# Controller.net
KiCad netlist of a schematic drawn in EAGLE
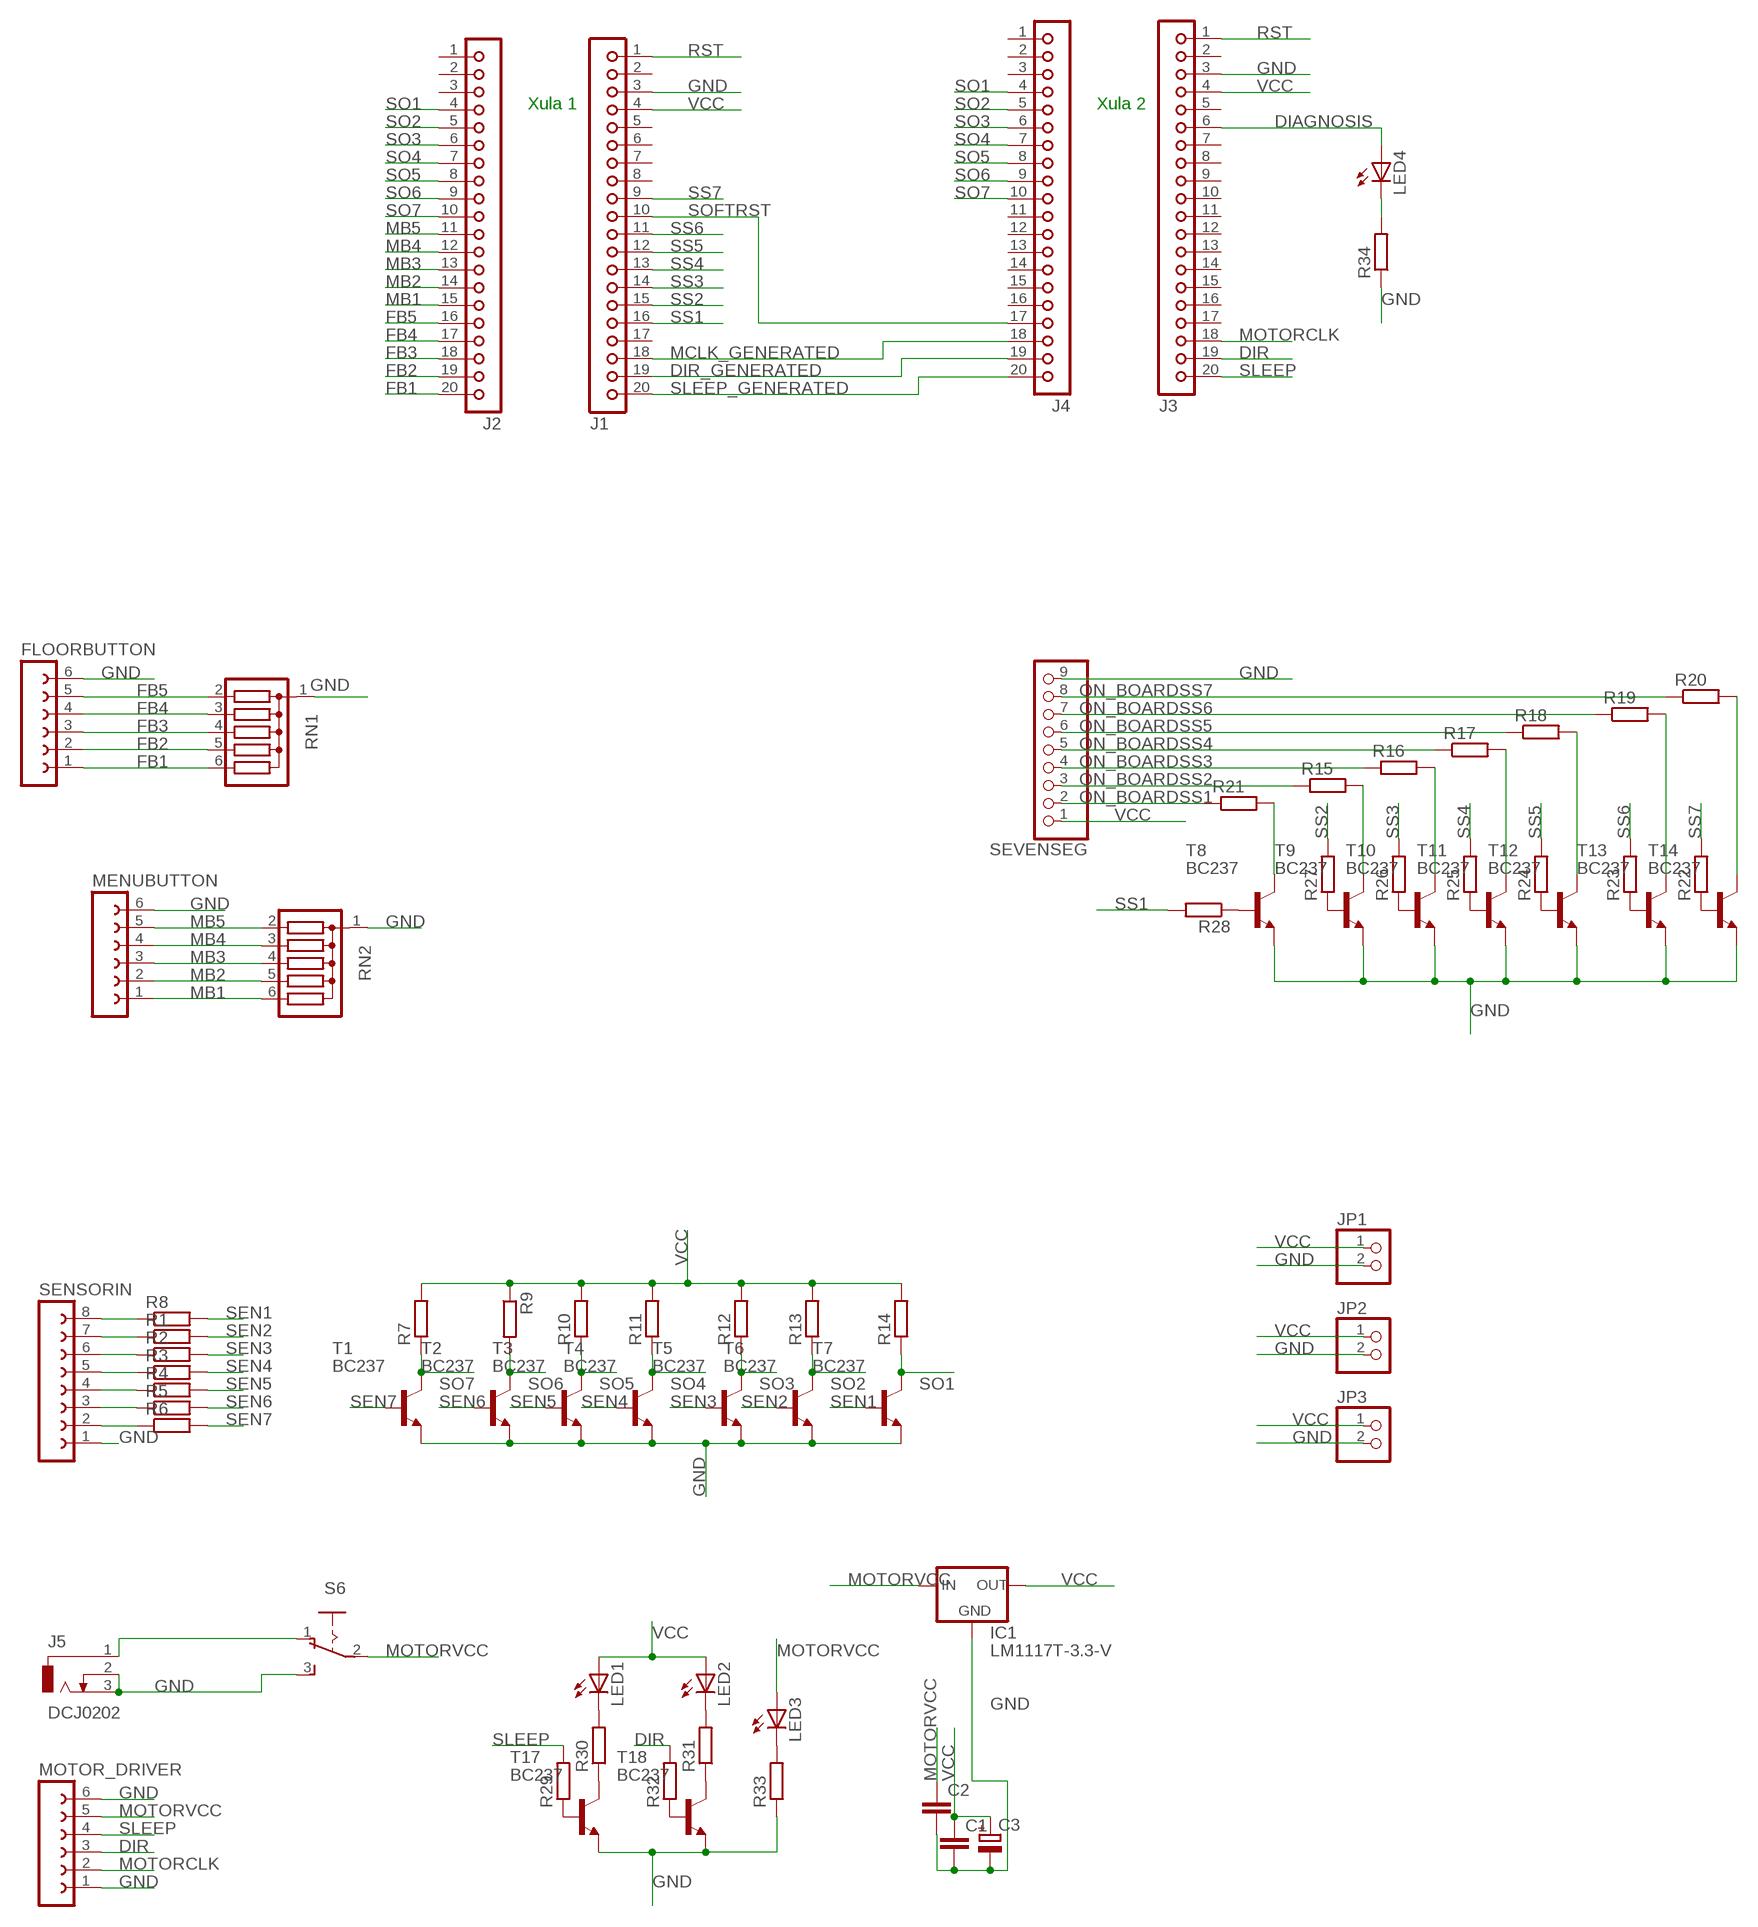
[diagram p0: schematic, sheet 1]

(export (version "E")
  (design (tool "Eeschema 10.0.6"))
  (components
    (comp (ref "C1")
      (value "C-EU025-025X050")
      (footprint "eagle-import:C025-025X050")
      (libsource (lib "eagle-import") (part "C-EU025-025X050"))
    )
    (comp (ref "C2")
      (value "C-EU025-025X050")
      (footprint "eagle-import:C025-025X050")
      (libsource (lib "eagle-import") (part "C-EU025-025X050"))
    )
    (comp (ref "C3")
      (value "CPOL-EUE3.5-8")
      (footprint "eagle-import:E3,5-8")
      (libsource (lib "eagle-import") (part "CPOL-EUE3.5-8"))
    )
    (comp (ref "FLOORBUTTON")
      (value "FE06-1")
      (footprint "eagle-import:FE06")
      (libsource (lib "eagle-import") (part "FE06-1"))
    )
    (comp (ref "IC1")
      (value "LM1117T-3.3-V")
      (footprint "eagle-import:TO220V")
      (libsource (lib "eagle-import") (part "LM1117T--V3.3"))
    )
    (comp (ref "J1")
      (value "JBK20")
      (footprint "eagle-import:JBK20")
      (libsource (lib "eagle-import") (part "JBK20"))
    )
    (comp (ref "J2")
      (value "JBK20")
      (footprint "eagle-import:JBK20")
      (libsource (lib "eagle-import") (part "JBK20"))
    )
    (comp (ref "J3")
      (value "JBK20")
      (footprint "eagle-import:JBK20")
      (libsource (lib "eagle-import") (part "JBK20"))
    )
    (comp (ref "J4")
      (value "JBK20")
      (footprint "eagle-import:JBK20")
      (libsource (lib "eagle-import") (part "JBK20"))
    )
    (comp (ref "J5")
      (value "DCJ0202")
      (footprint "eagle-import:DCJ0202")
      (libsource (lib "eagle-import") (part "DCJ0202"))
    )
    (comp (ref "JP1")
      (value "PINHD-1X2")
      (footprint "eagle-import:1X02")
      (libsource (lib "eagle-import") (part "PINHD-1X2"))
    )
    (comp (ref "JP2")
      (value "PINHD-1X2")
      (footprint "eagle-import:1X02")
      (libsource (lib "eagle-import") (part "PINHD-1X2"))
    )
    (comp (ref "JP3")
      (value "PINHD-1X2")
      (footprint "eagle-import:1X02")
      (libsource (lib "eagle-import") (part "PINHD-1X2"))
    )
    (comp (ref "LED1")
      (value "LED3MM")
      (footprint "eagle-import:LED3MM")
      (libsource (lib "eagle-import") (part "LED3MM"))
    )
    (comp (ref "LED2")
      (value "LED3MM")
      (footprint "eagle-import:LED3MM")
      (libsource (lib "eagle-import") (part "LED3MM"))
    )
    (comp (ref "LED3")
      (value "LED3MM")
      (footprint "eagle-import:LED3MM")
      (libsource (lib "eagle-import") (part "LED3MM"))
    )
    (comp (ref "LED4")
      (value "LED3MM")
      (footprint "eagle-import:LED3MM")
      (libsource (lib "eagle-import") (part "LED3MM"))
    )
    (comp (ref "MENUBUTTON")
      (value "FE06-1")
      (footprint "eagle-import:FE06")
      (libsource (lib "eagle-import") (part "FE06-1"))
    )
    (comp (ref "MOTOR_DRIVER")
      (value "FE06-1")
      (footprint "eagle-import:FE06")
      (libsource (lib "eagle-import") (part "FE06-1"))
    )
    (comp (ref "R1")
      (value "R-EU_0204/5")
      (footprint "eagle-import:0204_5")
      (libsource (lib "eagle-import") (part "R-EU_0204/5"))
    )
    (comp (ref "R2")
      (value "R-EU_0204/5")
      (footprint "eagle-import:0204_5")
      (libsource (lib "eagle-import") (part "R-EU_0204/5"))
    )
    (comp (ref "R3")
      (value "R-EU_0204/5")
      (footprint "eagle-import:0204_5")
      (libsource (lib "eagle-import") (part "R-EU_0204/5"))
    )
    (comp (ref "R4")
      (value "R-EU_0204/5")
      (footprint "eagle-import:0204_5")
      (libsource (lib "eagle-import") (part "R-EU_0204/5"))
    )
    (comp (ref "R5")
      (value "R-EU_0204/5")
      (footprint "eagle-import:0204_5")
      (libsource (lib "eagle-import") (part "R-EU_0204/5"))
    )
    (comp (ref "R6")
      (value "R-EU_0204/5")
      (footprint "eagle-import:0204_5")
      (libsource (lib "eagle-import") (part "R-EU_0204/5"))
    )
    (comp (ref "R7")
      (value "R-EU_0204/5")
      (footprint "eagle-import:0204_5")
      (libsource (lib "eagle-import") (part "R-EU_0204/5"))
    )
    (comp (ref "R8")
      (value "R-EU_0204/5")
      (footprint "eagle-import:0204_5")
      (libsource (lib "eagle-import") (part "R-EU_0204/5"))
    )
    (comp (ref "R9")
      (value "R-EU_0204/5")
      (footprint "eagle-import:0204_5")
      (libsource (lib "eagle-import") (part "R-EU_0204/5"))
    )
    (comp (ref "R10")
      (value "R-EU_0204/5")
      (footprint "eagle-import:0204_5")
      (libsource (lib "eagle-import") (part "R-EU_0204/5"))
    )
    (comp (ref "R11")
      (value "R-EU_0204/5")
      (footprint "eagle-import:0204_5")
      (libsource (lib "eagle-import") (part "R-EU_0204/5"))
    )
    (comp (ref "R12")
      (value "R-EU_0204/5")
      (footprint "eagle-import:0204_5")
      (libsource (lib "eagle-import") (part "R-EU_0204/5"))
    )
    (comp (ref "R13")
      (value "R-EU_0204/5")
      (footprint "eagle-import:0204_5")
      (libsource (lib "eagle-import") (part "R-EU_0204/5"))
    )
    (comp (ref "R14")
      (value "R-EU_0204/5")
      (footprint "eagle-import:0204_5")
      (libsource (lib "eagle-import") (part "R-EU_0204/5"))
    )
    (comp (ref "R15")
      (value "R-EU_0204/5")
      (footprint "eagle-import:0204_5")
      (libsource (lib "eagle-import") (part "R-EU_0204/5"))
    )
    (comp (ref "R16")
      (value "R-EU_0204/5")
      (footprint "eagle-import:0204_5")
      (libsource (lib "eagle-import") (part "R-EU_0204/5"))
    )
    (comp (ref "R17")
      (value "R-EU_0204/5")
      (footprint "eagle-import:0204_5")
      (libsource (lib "eagle-import") (part "R-EU_0204/5"))
    )
    (comp (ref "R18")
      (value "R-EU_0204/5")
      (footprint "eagle-import:0204_5")
      (libsource (lib "eagle-import") (part "R-EU_0204/5"))
    )
    (comp (ref "R19")
      (value "R-EU_0204/5")
      (footprint "eagle-import:0204_5")
      (libsource (lib "eagle-import") (part "R-EU_0204/5"))
    )
    (comp (ref "R20")
      (value "R-EU_0204/5")
      (footprint "eagle-import:0204_5")
      (libsource (lib "eagle-import") (part "R-EU_0204/5"))
    )
    (comp (ref "R21")
      (value "R-EU_0204/5")
      (footprint "eagle-import:0204_5")
      (libsource (lib "eagle-import") (part "R-EU_0204/5"))
    )
    (comp (ref "R22")
      (value "R-EU_0204/5")
      (footprint "eagle-import:0204_5")
      (libsource (lib "eagle-import") (part "R-EU_0204/5"))
    )
    (comp (ref "R23")
      (value "R-EU_0204/5")
      (footprint "eagle-import:0204_5")
      (libsource (lib "eagle-import") (part "R-EU_0204/5"))
    )
    (comp (ref "R24")
      (value "R-EU_0204/5")
      (footprint "eagle-import:0204_5")
      (libsource (lib "eagle-import") (part "R-EU_0204/5"))
    )
    (comp (ref "R25")
      (value "R-EU_0204/5")
      (footprint "eagle-import:0204_5")
      (libsource (lib "eagle-import") (part "R-EU_0204/5"))
    )
    (comp (ref "R26")
      (value "R-EU_0204/5")
      (footprint "eagle-import:0204_5")
      (libsource (lib "eagle-import") (part "R-EU_0204/5"))
    )
    (comp (ref "R27")
      (value "R-EU_0204/5")
      (footprint "eagle-import:0204_5")
      (libsource (lib "eagle-import") (part "R-EU_0204/5"))
    )
    (comp (ref "R28")
      (value "R-EU_0204/5")
      (footprint "eagle-import:0204_5")
      (libsource (lib "eagle-import") (part "R-EU_0204/5"))
    )
    (comp (ref "R29")
      (value "R-EU_0204/5")
      (footprint "eagle-import:0204_5")
      (libsource (lib "eagle-import") (part "R-EU_0204/5"))
    )
    (comp (ref "R30")
      (value "R-EU_0204/5")
      (footprint "eagle-import:0204_5")
      (libsource (lib "eagle-import") (part "R-EU_0204/5"))
    )
    (comp (ref "R31")
      (value "R-EU_0204/5")
      (footprint "eagle-import:0204_5")
      (libsource (lib "eagle-import") (part "R-EU_0204/5"))
    )
    (comp (ref "R32")
      (value "R-EU_0204/5")
      (footprint "eagle-import:0204_5")
      (libsource (lib "eagle-import") (part "R-EU_0204/5"))
    )
    (comp (ref "R33")
      (value "R-EU_0204/5")
      (footprint "eagle-import:0204_5")
      (libsource (lib "eagle-import") (part "R-EU_0204/5"))
    )
    (comp (ref "R34")
      (value "R-EU_0204/5")
      (footprint "eagle-import:0204_5")
      (libsource (lib "eagle-import") (part "R-EU_0204/5"))
    )
    (comp (ref "RN1")
      (value "G05R")
      (footprint "eagle-import:SIL6")
      (libsource (lib "eagle-import") (part "G05R"))
    )
    (comp (ref "RN2")
      (value "G05R")
      (footprint "eagle-import:SIL6")
      (libsource (lib "eagle-import") (part "G05R"))
    )
    (comp (ref "S6")
      (value "255SB")
      (footprint "eagle-import:255SB")
      (libsource (lib "eagle-import") (part "255SB"))
    )
    (comp (ref "SENSORIN")
      (value "FE08-1")
      (footprint "eagle-import:FE08")
      (libsource (lib "eagle-import") (part "FE08-1"))
    )
    (comp (ref "SEVENSEG")
      (value "PINHD-1X9")
      (footprint "eagle-import:1X09-BIG")
      (libsource (lib "eagle-import") (part "PINHD-1X9"))
    )
    (comp (ref "T1")
      (value "BC237")
      (footprint "eagle-import:TO92")
      (libsource (lib "eagle-import") (part "BC237"))
    )
    (comp (ref "T2")
      (value "BC237")
      (footprint "eagle-import:TO92")
      (libsource (lib "eagle-import") (part "BC237"))
    )
    (comp (ref "T3")
      (value "BC237")
      (footprint "eagle-import:TO92")
      (libsource (lib "eagle-import") (part "BC237"))
    )
    (comp (ref "T4")
      (value "BC237")
      (footprint "eagle-import:TO92")
      (libsource (lib "eagle-import") (part "BC237"))
    )
    (comp (ref "T5")
      (value "BC237")
      (footprint "eagle-import:TO92")
      (libsource (lib "eagle-import") (part "BC237"))
    )
    (comp (ref "T6")
      (value "BC237")
      (footprint "eagle-import:TO92")
      (libsource (lib "eagle-import") (part "BC237"))
    )
    (comp (ref "T7")
      (value "BC237")
      (footprint "eagle-import:TO92")
      (libsource (lib "eagle-import") (part "BC237"))
    )
    (comp (ref "T8")
      (value "BC237")
      (footprint "eagle-import:TO92")
      (libsource (lib "eagle-import") (part "BC237"))
    )
    (comp (ref "T9")
      (value "BC237")
      (footprint "eagle-import:TO92")
      (libsource (lib "eagle-import") (part "BC237"))
    )
    (comp (ref "T10")
      (value "BC237")
      (footprint "eagle-import:TO92")
      (libsource (lib "eagle-import") (part "BC237"))
    )
    (comp (ref "T11")
      (value "BC237")
      (footprint "eagle-import:TO92")
      (libsource (lib "eagle-import") (part "BC237"))
    )
    (comp (ref "T12")
      (value "BC237")
      (footprint "eagle-import:TO92")
      (libsource (lib "eagle-import") (part "BC237"))
    )
    (comp (ref "T13")
      (value "BC237")
      (footprint "eagle-import:TO92")
      (libsource (lib "eagle-import") (part "BC237"))
    )
    (comp (ref "T14")
      (value "BC237")
      (footprint "eagle-import:TO92")
      (libsource (lib "eagle-import") (part "BC237"))
    )
    (comp (ref "T17")
      (value "BC237")
      (footprint "eagle-import:TO92")
      (libsource (lib "eagle-import") (part "BC237"))
    )
    (comp (ref "T18")
      (value "BC237")
      (footprint "eagle-import:TO92")
      (libsource (lib "eagle-import") (part "BC237"))
    )
  )
  (nets
    (net (code "1") (name "/DIAGNOSIS") (class "Default")
      (node (ref "J3") (pin "6") (pinfunction "6_6") (pintype "passive"))
      (node (ref "LED4") (pin "A") (pinfunction "A_A") (pintype "passive"))
    )
    (net (code "2") (name "/DIR") (class "Default")
      (node (ref "J3") (pin "19") (pinfunction "19_19") (pintype "passive"))
      (node (ref "MOTOR_DRIVER") (pin "3") (pinfunction "3_3") (pintype "passive"))
      (node (ref "R32") (pin "2") (pinfunction "2_2") (pintype "passive"))
    )
    (net (code "3") (name "/DIR_GENERATED") (class "Default")
      (node (ref "J1") (pin "19") (pinfunction "19_19") (pintype "passive"))
      (node (ref "J4") (pin "19") (pinfunction "19_19") (pintype "passive"))
    )
    (net (code "4") (name "/FB1") (class "Default")
      (node (ref "FLOORBUTTON") (pin "1") (pinfunction "1_1") (pintype "passive"))
      (node (ref "J2") (pin "20") (pinfunction "20_20") (pintype "passive"))
      (node (ref "RN1") (pin "6") (pinfunction "6_6") (pintype "passive"))
    )
    (net (code "5") (name "/FB2") (class "Default")
      (node (ref "FLOORBUTTON") (pin "2") (pinfunction "2_2") (pintype "passive"))
      (node (ref "J2") (pin "19") (pinfunction "19_19") (pintype "passive"))
      (node (ref "RN1") (pin "5") (pinfunction "5_5") (pintype "passive"))
    )
    (net (code "6") (name "/FB3") (class "Default")
      (node (ref "FLOORBUTTON") (pin "3") (pinfunction "3_3") (pintype "passive"))
      (node (ref "J2") (pin "18") (pinfunction "18_18") (pintype "passive"))
      (node (ref "RN1") (pin "4") (pinfunction "4_4") (pintype "passive"))
    )
    (net (code "7") (name "/FB4") (class "Default")
      (node (ref "FLOORBUTTON") (pin "4") (pinfunction "4_4") (pintype "passive"))
      (node (ref "J2") (pin "17") (pinfunction "17_17") (pintype "passive"))
      (node (ref "RN1") (pin "3") (pinfunction "3_3") (pintype "passive"))
    )
    (net (code "8") (name "/FB5") (class "Default")
      (node (ref "FLOORBUTTON") (pin "5") (pinfunction "5_5") (pintype "passive"))
      (node (ref "J2") (pin "16") (pinfunction "16_16") (pintype "passive"))
      (node (ref "RN1") (pin "2") (pinfunction "2_2") (pintype "passive"))
    )
    (net (code "9") (name "/GND") (class "Default")
      (node (ref "C1") (pin "2") (pinfunction "2_2") (pintype "passive"))
      (node (ref "C2") (pin "2") (pinfunction "2_2") (pintype "passive"))
      (node (ref "C3") (pin "-") (pinfunction "-_-") (pintype "passive"))
      (node (ref "FLOORBUTTON") (pin "6") (pinfunction "6_6") (pintype "passive"))
      (node (ref "IC1") (pin "1") (pinfunction "GND_1") (pintype "input"))
      (node (ref "J1") (pin "3") (pinfunction "3_3") (pintype "passive"))
      (node (ref "J3") (pin "3") (pinfunction "3_3") (pintype "passive"))
      (node (ref "J5") (pin "2") (pinfunction "2_2") (pintype "passive"))
      (node (ref "J5") (pin "3") (pinfunction "3_3") (pintype "passive"))
      (node (ref "JP1") (pin "2") (pinfunction "2_2") (pintype "passive"))
      (node (ref "JP2") (pin "2") (pinfunction "2_2") (pintype "passive"))
      (node (ref "JP3") (pin "2") (pinfunction "2_2") (pintype "passive"))
      (node (ref "MENUBUTTON") (pin "6") (pinfunction "6_6") (pintype "passive"))
      (node (ref "MOTOR_DRIVER") (pin "1") (pinfunction "1_1") (pintype "passive"))
      (node (ref "MOTOR_DRIVER") (pin "6") (pinfunction "6_6") (pintype "passive"))
      (node (ref "R33") (pin "1") (pinfunction "1_1") (pintype "passive"))
      (node (ref "R34") (pin "1") (pinfunction "1_1") (pintype "passive"))
      (node (ref "RN1") (pin "1") (pinfunction "1_1") (pintype "passive"))
      (node (ref "RN2") (pin "1") (pinfunction "1_1") (pintype "passive"))
      (node (ref "S6") (pin "3") (pinfunction "S_3") (pintype "passive"))
      (node (ref "SENSORIN") (pin "1") (pinfunction "1_1") (pintype "passive"))
      (node (ref "SEVENSEG") (pin "9") (pinfunction "9_9") (pintype "passive"))
      (node (ref "T1") (pin "1") (pinfunction "E_1") (pintype "passive"))
      (node (ref "T10") (pin "1") (pinfunction "E_1") (pintype "passive"))
      (node (ref "T11") (pin "1") (pinfunction "E_1") (pintype "passive"))
      (node (ref "T12") (pin "1") (pinfunction "E_1") (pintype "passive"))
      (node (ref "T13") (pin "1") (pinfunction "E_1") (pintype "passive"))
      (node (ref "T14") (pin "1") (pinfunction "E_1") (pintype "passive"))
      (node (ref "T17") (pin "1") (pinfunction "E_1") (pintype "passive"))
      (node (ref "T18") (pin "1") (pinfunction "E_1") (pintype "passive"))
      (node (ref "T2") (pin "1") (pinfunction "E_1") (pintype "passive"))
      (node (ref "T3") (pin "1") (pinfunction "E_1") (pintype "passive"))
      (node (ref "T4") (pin "1") (pinfunction "E_1") (pintype "passive"))
      (node (ref "T5") (pin "1") (pinfunction "E_1") (pintype "passive"))
      (node (ref "T6") (pin "1") (pinfunction "E_1") (pintype "passive"))
      (node (ref "T7") (pin "1") (pinfunction "E_1") (pintype "passive"))
      (node (ref "T8") (pin "1") (pinfunction "E_1") (pintype "passive"))
      (node (ref "T9") (pin "1") (pinfunction "E_1") (pintype "passive"))
    )
    (net (code "10") (name "/MB1") (class "Default")
      (node (ref "J2") (pin "15") (pinfunction "15_15") (pintype "passive"))
      (node (ref "MENUBUTTON") (pin "1") (pinfunction "1_1") (pintype "passive"))
      (node (ref "RN2") (pin "6") (pinfunction "6_6") (pintype "passive"))
    )
    (net (code "11") (name "/MB2") (class "Default")
      (node (ref "J2") (pin "14") (pinfunction "14_14") (pintype "passive"))
      (node (ref "MENUBUTTON") (pin "2") (pinfunction "2_2") (pintype "passive"))
      (node (ref "RN2") (pin "5") (pinfunction "5_5") (pintype "passive"))
    )
    (net (code "12") (name "/MB3") (class "Default")
      (node (ref "J2") (pin "13") (pinfunction "13_13") (pintype "passive"))
      (node (ref "MENUBUTTON") (pin "3") (pinfunction "3_3") (pintype "passive"))
      (node (ref "RN2") (pin "4") (pinfunction "4_4") (pintype "passive"))
    )
    (net (code "13") (name "/MB4") (class "Default")
      (node (ref "J2") (pin "12") (pinfunction "12_12") (pintype "passive"))
      (node (ref "MENUBUTTON") (pin "4") (pinfunction "4_4") (pintype "passive"))
      (node (ref "RN2") (pin "3") (pinfunction "3_3") (pintype "passive"))
    )
    (net (code "14") (name "/MB5") (class "Default")
      (node (ref "J2") (pin "11") (pinfunction "11_11") (pintype "passive"))
      (node (ref "MENUBUTTON") (pin "5") (pinfunction "5_5") (pintype "passive"))
      (node (ref "RN2") (pin "2") (pinfunction "2_2") (pintype "passive"))
    )
    (net (code "15") (name "/MCLK_GENERATED") (class "Default")
      (node (ref "J1") (pin "18") (pinfunction "18_18") (pintype "passive"))
      (node (ref "J4") (pin "18") (pinfunction "18_18") (pintype "passive"))
    )
    (net (code "16") (name "/MOTORCLK") (class "Default")
      (node (ref "J3") (pin "18") (pinfunction "18_18") (pintype "passive"))
      (node (ref "MOTOR_DRIVER") (pin "2") (pinfunction "2_2") (pintype "passive"))
    )
    (net (code "17") (name "/MOTORVCC") (class "Default")
      (node (ref "C2") (pin "1") (pinfunction "1_1") (pintype "passive"))
      (node (ref "IC1") (pin "3") (pinfunction "IN_3") (pintype "input"))
      (node (ref "LED3") (pin "A") (pinfunction "A_A") (pintype "passive"))
      (node (ref "MOTOR_DRIVER") (pin "5") (pinfunction "5_5") (pintype "passive"))
      (node (ref "S6") (pin "2") (pinfunction "P_2") (pintype "passive"))
    )
    (net (code "18") (name "/ON_BOARDSS1") (class "Default")
      (node (ref "R21") (pin "1") (pinfunction "1_1") (pintype "passive"))
      (node (ref "SEVENSEG") (pin "2") (pinfunction "2_2") (pintype "passive"))
    )
    (net (code "19") (name "/ON_BOARDSS2") (class "Default")
      (node (ref "R15") (pin "1") (pinfunction "1_1") (pintype "passive"))
      (node (ref "SEVENSEG") (pin "3") (pinfunction "3_3") (pintype "passive"))
    )
    (net (code "20") (name "/ON_BOARDSS3") (class "Default")
      (node (ref "R16") (pin "1") (pinfunction "1_1") (pintype "passive"))
      (node (ref "SEVENSEG") (pin "4") (pinfunction "4_4") (pintype "passive"))
    )
    (net (code "21") (name "/ON_BOARDSS4") (class "Default")
      (node (ref "R17") (pin "1") (pinfunction "1_1") (pintype "passive"))
      (node (ref "SEVENSEG") (pin "5") (pinfunction "5_5") (pintype "passive"))
    )
    (net (code "22") (name "/ON_BOARDSS5") (class "Default")
      (node (ref "R18") (pin "1") (pinfunction "1_1") (pintype "passive"))
      (node (ref "SEVENSEG") (pin "6") (pinfunction "6_6") (pintype "passive"))
    )
    (net (code "23") (name "/ON_BOARDSS6") (class "Default")
      (node (ref "R19") (pin "1") (pinfunction "1_1") (pintype "passive"))
      (node (ref "SEVENSEG") (pin "7") (pinfunction "7_7") (pintype "passive"))
    )
    (net (code "24") (name "/ON_BOARDSS7") (class "Default")
      (node (ref "R20") (pin "1") (pinfunction "1_1") (pintype "passive"))
      (node (ref "SEVENSEG") (pin "8") (pinfunction "8_8") (pintype "passive"))
    )
    (net (code "25") (name "/RST") (class "Default")
      (node (ref "J1") (pin "1") (pinfunction "1_1") (pintype "passive"))
      (node (ref "J3") (pin "1") (pinfunction "1_1") (pintype "passive"))
    )
    (net (code "26") (name "/SEN1") (class "Default")
      (node (ref "R8") (pin "2") (pinfunction "2_2") (pintype "passive"))
      (node (ref "T7") (pin "2") (pinfunction "B_2") (pintype "passive"))
    )
    (net (code "27") (name "/SEN2") (class "Default")
      (node (ref "R1") (pin "2") (pinfunction "2_2") (pintype "passive"))
      (node (ref "T6") (pin "2") (pinfunction "B_2") (pintype "passive"))
    )
    (net (code "28") (name "/SEN3") (class "Default")
      (node (ref "R2") (pin "2") (pinfunction "2_2") (pintype "passive"))
      (node (ref "T5") (pin "2") (pinfunction "B_2") (pintype "passive"))
    )
    (net (code "29") (name "/SEN4") (class "Default")
      (node (ref "R3") (pin "2") (pinfunction "2_2") (pintype "passive"))
      (node (ref "T4") (pin "2") (pinfunction "B_2") (pintype "passive"))
    )
    (net (code "30") (name "/SEN5") (class "Default")
      (node (ref "R4") (pin "2") (pinfunction "2_2") (pintype "passive"))
      (node (ref "T3") (pin "2") (pinfunction "B_2") (pintype "passive"))
    )
    (net (code "31") (name "/SEN6") (class "Default")
      (node (ref "R5") (pin "2") (pinfunction "2_2") (pintype "passive"))
      (node (ref "T2") (pin "2") (pinfunction "B_2") (pintype "passive"))
    )
    (net (code "32") (name "/SEN7") (class "Default")
      (node (ref "R6") (pin "2") (pinfunction "2_2") (pintype "passive"))
      (node (ref "T1") (pin "2") (pinfunction "B_2") (pintype "passive"))
    )
    (net (code "33") (name "/SLEEP") (class "Default")
      (node (ref "J3") (pin "20") (pinfunction "20_20") (pintype "passive"))
      (node (ref "MOTOR_DRIVER") (pin "4") (pinfunction "4_4") (pintype "passive"))
      (node (ref "R29") (pin "2") (pinfunction "2_2") (pintype "passive"))
    )
    (net (code "34") (name "/SLEEP_GENERATED") (class "Default")
      (node (ref "J1") (pin "20") (pinfunction "20_20") (pintype "passive"))
      (node (ref "J4") (pin "20") (pinfunction "20_20") (pintype "passive"))
    )
    (net (code "35") (name "/SO1") (class "Default")
      (node (ref "J2") (pin "4") (pinfunction "4_4") (pintype "passive"))
      (node (ref "J4") (pin "4") (pinfunction "4_4") (pintype "passive"))
      (node (ref "R14") (pin "1") (pinfunction "1_1") (pintype "passive"))
      (node (ref "T7") (pin "3") (pinfunction "C_3") (pintype "passive"))
    )
    (net (code "36") (name "/SO2") (class "Default")
      (node (ref "J2") (pin "5") (pinfunction "5_5") (pintype "passive"))
      (node (ref "J4") (pin "5") (pinfunction "5_5") (pintype "passive"))
      (node (ref "R13") (pin "1") (pinfunction "1_1") (pintype "passive"))
      (node (ref "T6") (pin "3") (pinfunction "C_3") (pintype "passive"))
    )
    (net (code "37") (name "/SO3") (class "Default")
      (node (ref "J2") (pin "6") (pinfunction "6_6") (pintype "passive"))
      (node (ref "J4") (pin "6") (pinfunction "6_6") (pintype "passive"))
      (node (ref "R12") (pin "1") (pinfunction "1_1") (pintype "passive"))
      (node (ref "T5") (pin "3") (pinfunction "C_3") (pintype "passive"))
    )
    (net (code "38") (name "/SO4") (class "Default")
      (node (ref "J2") (pin "7") (pinfunction "7_7") (pintype "passive"))
      (node (ref "J4") (pin "7") (pinfunction "7_7") (pintype "passive"))
      (node (ref "R11") (pin "1") (pinfunction "1_1") (pintype "passive"))
      (node (ref "T4") (pin "3") (pinfunction "C_3") (pintype "passive"))
    )
    (net (code "39") (name "/SO5") (class "Default")
      (node (ref "J2") (pin "8") (pinfunction "8_8") (pintype "passive"))
      (node (ref "J4") (pin "8") (pinfunction "8_8") (pintype "passive"))
      (node (ref "R10") (pin "1") (pinfunction "1_1") (pintype "passive"))
      (node (ref "T3") (pin "3") (pinfunction "C_3") (pintype "passive"))
    )
    (net (code "40") (name "/SO6") (class "Default")
      (node (ref "J2") (pin "9") (pinfunction "9_9") (pintype "passive"))
      (node (ref "J4") (pin "9") (pinfunction "9_9") (pintype "passive"))
      (node (ref "R9") (pin "2") (pinfunction "2_2") (pintype "passive"))
      (node (ref "T2") (pin "3") (pinfunction "C_3") (pintype "passive"))
    )
    (net (code "41") (name "/SO7") (class "Default")
      (node (ref "J2") (pin "10") (pinfunction "10_10") (pintype "passive"))
      (node (ref "J4") (pin "10") (pinfunction "10_10") (pintype "passive"))
      (node (ref "R7") (pin "1") (pinfunction "1_1") (pintype "passive"))
      (node (ref "T1") (pin "3") (pinfunction "C_3") (pintype "passive"))
    )
    (net (code "42") (name "/SOFTRST") (class "Default")
      (node (ref "J1") (pin "10") (pinfunction "10_10") (pintype "passive"))
      (node (ref "J4") (pin "17") (pinfunction "17_17") (pintype "passive"))
    )
    (net (code "43") (name "/SS1") (class "Default")
      (node (ref "J1") (pin "16") (pinfunction "16_16") (pintype "passive"))
      (node (ref "R28") (pin "2") (pinfunction "2_2") (pintype "passive"))
    )
    (net (code "44") (name "/SS2") (class "Default")
      (node (ref "J1") (pin "15") (pinfunction "15_15") (pintype "passive"))
      (node (ref "R27") (pin "2") (pinfunction "2_2") (pintype "passive"))
    )
    (net (code "45") (name "/SS3") (class "Default")
      (node (ref "J1") (pin "14") (pinfunction "14_14") (pintype "passive"))
      (node (ref "R26") (pin "2") (pinfunction "2_2") (pintype "passive"))
    )
    (net (code "46") (name "/SS4") (class "Default")
      (node (ref "J1") (pin "13") (pinfunction "13_13") (pintype "passive"))
      (node (ref "R25") (pin "2") (pinfunction "2_2") (pintype "passive"))
    )
    (net (code "47") (name "/SS5") (class "Default")
      (node (ref "J1") (pin "12") (pinfunction "12_12") (pintype "passive"))
      (node (ref "R24") (pin "2") (pinfunction "2_2") (pintype "passive"))
    )
    (net (code "48") (name "/SS6") (class "Default")
      (node (ref "J1") (pin "11") (pinfunction "11_11") (pintype "passive"))
      (node (ref "R23") (pin "2") (pinfunction "2_2") (pintype "passive"))
    )
    (net (code "49") (name "/SS7") (class "Default")
      (node (ref "J1") (pin "9") (pinfunction "9_9") (pintype "passive"))
      (node (ref "R22") (pin "2") (pinfunction "2_2") (pintype "passive"))
    )
    (net (code "50") (name "/VCC") (class "Default")
      (node (ref "C1") (pin "1") (pinfunction "1_1") (pintype "passive"))
      (node (ref "C3") (pin "+") (pinfunction "+_+") (pintype "passive"))
      (node (ref "IC1") (pin "2") (pinfunction "OUT_2") (pintype "passive"))
      (node (ref "J1") (pin "4") (pinfunction "4_4") (pintype "passive"))
      (node (ref "J3") (pin "4") (pinfunction "4_4") (pintype "passive"))
      (node (ref "JP1") (pin "1") (pinfunction "1_1") (pintype "passive"))
      (node (ref "JP2") (pin "1") (pinfunction "1_1") (pintype "passive"))
      (node (ref "JP3") (pin "1") (pinfunction "1_1") (pintype "passive"))
      (node (ref "LED1") (pin "A") (pinfunction "A_A") (pintype "passive"))
      (node (ref "LED2") (pin "A") (pinfunction "A_A") (pintype "passive"))
      (node (ref "R10") (pin "2") (pinfunction "2_2") (pintype "passive"))
      (node (ref "R11") (pin "2") (pinfunction "2_2") (pintype "passive"))
      (node (ref "R12") (pin "2") (pinfunction "2_2") (pintype "passive"))
      (node (ref "R13") (pin "2") (pinfunction "2_2") (pintype "passive"))
      (node (ref "R14") (pin "2") (pinfunction "2_2") (pintype "passive"))
      (node (ref "R7") (pin "2") (pinfunction "2_2") (pintype "passive"))
      (node (ref "R9") (pin "1") (pinfunction "1_1") (pintype "passive"))
      (node (ref "SEVENSEG") (pin "1") (pinfunction "1_1") (pintype "passive"))
    )
    (net (code "51") (name "Net-(LED1-C)") (class "Default")
      (node (ref "LED1") (pin "K") (pinfunction "C_K") (pintype "passive"))
      (node (ref "R30") (pin "2") (pinfunction "2_2") (pintype "passive"))
    )
    (net (code "52") (name "Net-(LED2-C)") (class "Default")
      (node (ref "LED2") (pin "K") (pinfunction "C_K") (pintype "passive"))
      (node (ref "R31") (pin "2") (pinfunction "2_2") (pintype "passive"))
    )
    (net (code "53") (name "Net-(LED3-C)") (class "Default")
      (node (ref "LED3") (pin "K") (pinfunction "C_K") (pintype "passive"))
      (node (ref "R33") (pin "2") (pinfunction "2_2") (pintype "passive"))
    )
    (net (code "54") (name "Net-(LED4-C)") (class "Default")
      (node (ref "LED4") (pin "K") (pinfunction "C_K") (pintype "passive"))
      (node (ref "R34") (pin "2") (pinfunction "2_2") (pintype "passive"))
    )
    (net (code "55") (name "Net-(R1-Pad1)") (class "Default")
      (node (ref "R1") (pin "1") (pinfunction "1_1") (pintype "passive"))
      (node (ref "SENSORIN") (pin "7") (pinfunction "7_7") (pintype "passive"))
    )
    (net (code "56") (name "Net-(R2-Pad1)") (class "Default")
      (node (ref "R2") (pin "1") (pinfunction "1_1") (pintype "passive"))
      (node (ref "SENSORIN") (pin "6") (pinfunction "6_6") (pintype "passive"))
    )
    (net (code "57") (name "Net-(R3-Pad1)") (class "Default")
      (node (ref "R3") (pin "1") (pinfunction "1_1") (pintype "passive"))
      (node (ref "SENSORIN") (pin "5") (pinfunction "5_5") (pintype "passive"))
    )
    (net (code "58") (name "Net-(R4-Pad1)") (class "Default")
      (node (ref "R4") (pin "1") (pinfunction "1_1") (pintype "passive"))
      (node (ref "SENSORIN") (pin "4") (pinfunction "4_4") (pintype "passive"))
    )
    (net (code "59") (name "Net-(R5-Pad1)") (class "Default")
      (node (ref "R5") (pin "1") (pinfunction "1_1") (pintype "passive"))
      (node (ref "SENSORIN") (pin "3") (pinfunction "3_3") (pintype "passive"))
    )
    (net (code "60") (name "Net-(R6-Pad1)") (class "Default")
      (node (ref "R6") (pin "1") (pinfunction "1_1") (pintype "passive"))
      (node (ref "SENSORIN") (pin "2") (pinfunction "2_2") (pintype "passive"))
    )
    (net (code "61") (name "Net-(R8-Pad1)") (class "Default")
      (node (ref "R8") (pin "1") (pinfunction "1_1") (pintype "passive"))
      (node (ref "SENSORIN") (pin "8") (pinfunction "8_8") (pintype "passive"))
    )
    (net (code "62") (name "Net-(S6-O)") (class "Default")
      (node (ref "J5") (pin "1") (pinfunction "1_1") (pintype "passive"))
      (node (ref "S6") (pin "1") (pinfunction "O_1") (pintype "passive"))
    )
    (net (code "63") (name "Net-(T8-B)") (class "Default")
      (node (ref "R28") (pin "1") (pinfunction "1_1") (pintype "passive"))
      (node (ref "T8") (pin "2") (pinfunction "B_2") (pintype "passive"))
    )
    (net (code "64") (name "Net-(T8-C)") (class "Default")
      (node (ref "R21") (pin "2") (pinfunction "2_2") (pintype "passive"))
      (node (ref "T8") (pin "3") (pinfunction "C_3") (pintype "passive"))
    )
    (net (code "65") (name "Net-(T9-B)") (class "Default")
      (node (ref "R27") (pin "1") (pinfunction "1_1") (pintype "passive"))
      (node (ref "T9") (pin "2") (pinfunction "B_2") (pintype "passive"))
    )
    (net (code "66") (name "Net-(T9-C)") (class "Default")
      (node (ref "R15") (pin "2") (pinfunction "2_2") (pintype "passive"))
      (node (ref "T9") (pin "3") (pinfunction "C_3") (pintype "passive"))
    )
    (net (code "67") (name "Net-(T10-B)") (class "Default")
      (node (ref "R26") (pin "1") (pinfunction "1_1") (pintype "passive"))
      (node (ref "T10") (pin "2") (pinfunction "B_2") (pintype "passive"))
    )
    (net (code "68") (name "Net-(T10-C)") (class "Default")
      (node (ref "R16") (pin "2") (pinfunction "2_2") (pintype "passive"))
      (node (ref "T10") (pin "3") (pinfunction "C_3") (pintype "passive"))
    )
    (net (code "69") (name "Net-(T11-B)") (class "Default")
      (node (ref "R25") (pin "1") (pinfunction "1_1") (pintype "passive"))
      (node (ref "T11") (pin "2") (pinfunction "B_2") (pintype "passive"))
    )
    (net (code "70") (name "Net-(T11-C)") (class "Default")
      (node (ref "R17") (pin "2") (pinfunction "2_2") (pintype "passive"))
      (node (ref "T11") (pin "3") (pinfunction "C_3") (pintype "passive"))
    )
    (net (code "71") (name "Net-(T12-B)") (class "Default")
      (node (ref "R24") (pin "1") (pinfunction "1_1") (pintype "passive"))
      (node (ref "T12") (pin "2") (pinfunction "B_2") (pintype "passive"))
    )
    (net (code "72") (name "Net-(T12-C)") (class "Default")
      (node (ref "R18") (pin "2") (pinfunction "2_2") (pintype "passive"))
      (node (ref "T12") (pin "3") (pinfunction "C_3") (pintype "passive"))
    )
    (net (code "73") (name "Net-(T13-B)") (class "Default")
      (node (ref "R23") (pin "1") (pinfunction "1_1") (pintype "passive"))
      (node (ref "T13") (pin "2") (pinfunction "B_2") (pintype "passive"))
    )
    (net (code "74") (name "Net-(T13-C)") (class "Default")
      (node (ref "R19") (pin "2") (pinfunction "2_2") (pintype "passive"))
      (node (ref "T13") (pin "3") (pinfunction "C_3") (pintype "passive"))
    )
    (net (code "75") (name "Net-(T14-B)") (class "Default")
      (node (ref "R22") (pin "1") (pinfunction "1_1") (pintype "passive"))
      (node (ref "T14") (pin "2") (pinfunction "B_2") (pintype "passive"))
    )
    (net (code "76") (name "Net-(T14-C)") (class "Default")
      (node (ref "R20") (pin "2") (pinfunction "2_2") (pintype "passive"))
      (node (ref "T14") (pin "3") (pinfunction "C_3") (pintype "passive"))
    )
    (net (code "77") (name "Net-(T17-B)") (class "Default")
      (node (ref "R29") (pin "1") (pinfunction "1_1") (pintype "passive"))
      (node (ref "T17") (pin "2") (pinfunction "B_2") (pintype "passive"))
    )
    (net (code "78") (name "Net-(T17-C)") (class "Default")
      (node (ref "R30") (pin "1") (pinfunction "1_1") (pintype "passive"))
      (node (ref "T17") (pin "3") (pinfunction "C_3") (pintype "passive"))
    )
    (net (code "79") (name "Net-(T18-B)") (class "Default")
      (node (ref "R32") (pin "1") (pinfunction "1_1") (pintype "passive"))
      (node (ref "T18") (pin "2") (pinfunction "B_2") (pintype "passive"))
    )
    (net (code "80") (name "Net-(T18-C)") (class "Default")
      (node (ref "R31") (pin "1") (pinfunction "1_1") (pintype "passive"))
      (node (ref "T18") (pin "3") (pinfunction "C_3") (pintype "passive"))
    )
    (net (code "81") (name "unconnected-(J1-Pad2)") (class "Default")
      (node (ref "J1") (pin "2") (pinfunction "2_2") (pintype "passive"))
    )
    (net (code "82") (name "unconnected-(J1-Pad5)") (class "Default")
      (node (ref "J1") (pin "5") (pinfunction "5_5") (pintype "passive"))
    )
    (net (code "83") (name "unconnected-(J1-Pad6)") (class "Default")
      (node (ref "J1") (pin "6") (pinfunction "6_6") (pintype "passive"))
    )
    (net (code "84") (name "unconnected-(J1-Pad7)") (class "Default")
      (node (ref "J1") (pin "7") (pinfunction "7_7") (pintype "passive"))
    )
    (net (code "85") (name "unconnected-(J1-Pad8)") (class "Default")
      (node (ref "J1") (pin "8") (pinfunction "8_8") (pintype "passive"))
    )
    (net (code "86") (name "unconnected-(J1-Pad17)") (class "Default")
      (node (ref "J1") (pin "17") (pinfunction "17_17") (pintype "passive"))
    )
    (net (code "87") (name "unconnected-(J2-Pad1)") (class "Default")
      (node (ref "J2") (pin "1") (pinfunction "1_1") (pintype "passive"))
    )
    (net (code "88") (name "unconnected-(J2-Pad2)") (class "Default")
      (node (ref "J2") (pin "2") (pinfunction "2_2") (pintype "passive"))
    )
    (net (code "89") (name "unconnected-(J2-Pad3)") (class "Default")
      (node (ref "J2") (pin "3") (pinfunction "3_3") (pintype "passive"))
    )
    (net (code "90") (name "unconnected-(J3-Pad2)") (class "Default")
      (node (ref "J3") (pin "2") (pinfunction "2_2") (pintype "passive"))
    )
    (net (code "91") (name "unconnected-(J3-Pad5)") (class "Default")
      (node (ref "J3") (pin "5") (pinfunction "5_5") (pintype "passive"))
    )
    (net (code "92") (name "unconnected-(J3-Pad7)") (class "Default")
      (node (ref "J3") (pin "7") (pinfunction "7_7") (pintype "passive"))
    )
    (net (code "93") (name "unconnected-(J3-Pad8)") (class "Default")
      (node (ref "J3") (pin "8") (pinfunction "8_8") (pintype "passive"))
    )
    (net (code "94") (name "unconnected-(J3-Pad9)") (class "Default")
      (node (ref "J3") (pin "9") (pinfunction "9_9") (pintype "passive"))
    )
    (net (code "95") (name "unconnected-(J3-Pad10)") (class "Default")
      (node (ref "J3") (pin "10") (pinfunction "10_10") (pintype "passive"))
    )
    (net (code "96") (name "unconnected-(J3-Pad11)") (class "Default")
      (node (ref "J3") (pin "11") (pinfunction "11_11") (pintype "passive"))
    )
    (net (code "97") (name "unconnected-(J3-Pad12)") (class "Default")
      (node (ref "J3") (pin "12") (pinfunction "12_12") (pintype "passive"))
    )
    (net (code "98") (name "unconnected-(J3-Pad13)") (class "Default")
      (node (ref "J3") (pin "13") (pinfunction "13_13") (pintype "passive"))
    )
    (net (code "99") (name "unconnected-(J3-Pad14)") (class "Default")
      (node (ref "J3") (pin "14") (pinfunction "14_14") (pintype "passive"))
    )
    (net (code "100") (name "unconnected-(J3-Pad15)") (class "Default")
      (node (ref "J3") (pin "15") (pinfunction "15_15") (pintype "passive"))
    )
    (net (code "101") (name "unconnected-(J3-Pad16)") (class "Default")
      (node (ref "J3") (pin "16") (pinfunction "16_16") (pintype "passive"))
    )
    (net (code "102") (name "unconnected-(J3-Pad17)") (class "Default")
      (node (ref "J3") (pin "17") (pinfunction "17_17") (pintype "passive"))
    )
    (net (code "103") (name "unconnected-(J4-Pad1)") (class "Default")
      (node (ref "J4") (pin "1") (pinfunction "1_1") (pintype "passive"))
    )
    (net (code "104") (name "unconnected-(J4-Pad2)") (class "Default")
      (node (ref "J4") (pin "2") (pinfunction "2_2") (pintype "passive"))
    )
    (net (code "105") (name "unconnected-(J4-Pad3)") (class "Default")
      (node (ref "J4") (pin "3") (pinfunction "3_3") (pintype "passive"))
    )
    (net (code "106") (name "unconnected-(J4-Pad11)") (class "Default")
      (node (ref "J4") (pin "11") (pinfunction "11_11") (pintype "passive"))
    )
    (net (code "107") (name "unconnected-(J4-Pad12)") (class "Default")
      (node (ref "J4") (pin "12") (pinfunction "12_12") (pintype "passive"))
    )
    (net (code "108") (name "unconnected-(J4-Pad13)") (class "Default")
      (node (ref "J4") (pin "13") (pinfunction "13_13") (pintype "passive"))
    )
    (net (code "109") (name "unconnected-(J4-Pad14)") (class "Default")
      (node (ref "J4") (pin "14") (pinfunction "14_14") (pintype "passive"))
    )
    (net (code "110") (name "unconnected-(J4-Pad15)") (class "Default")
      (node (ref "J4") (pin "15") (pinfunction "15_15") (pintype "passive"))
    )
    (net (code "111") (name "unconnected-(J4-Pad16)") (class "Default")
      (node (ref "J4") (pin "16") (pinfunction "16_16") (pintype "passive"))
    )
  )
)
